# 07_USB_OTG.net
KiCad netlist of a schematic drawn in Altium Designer
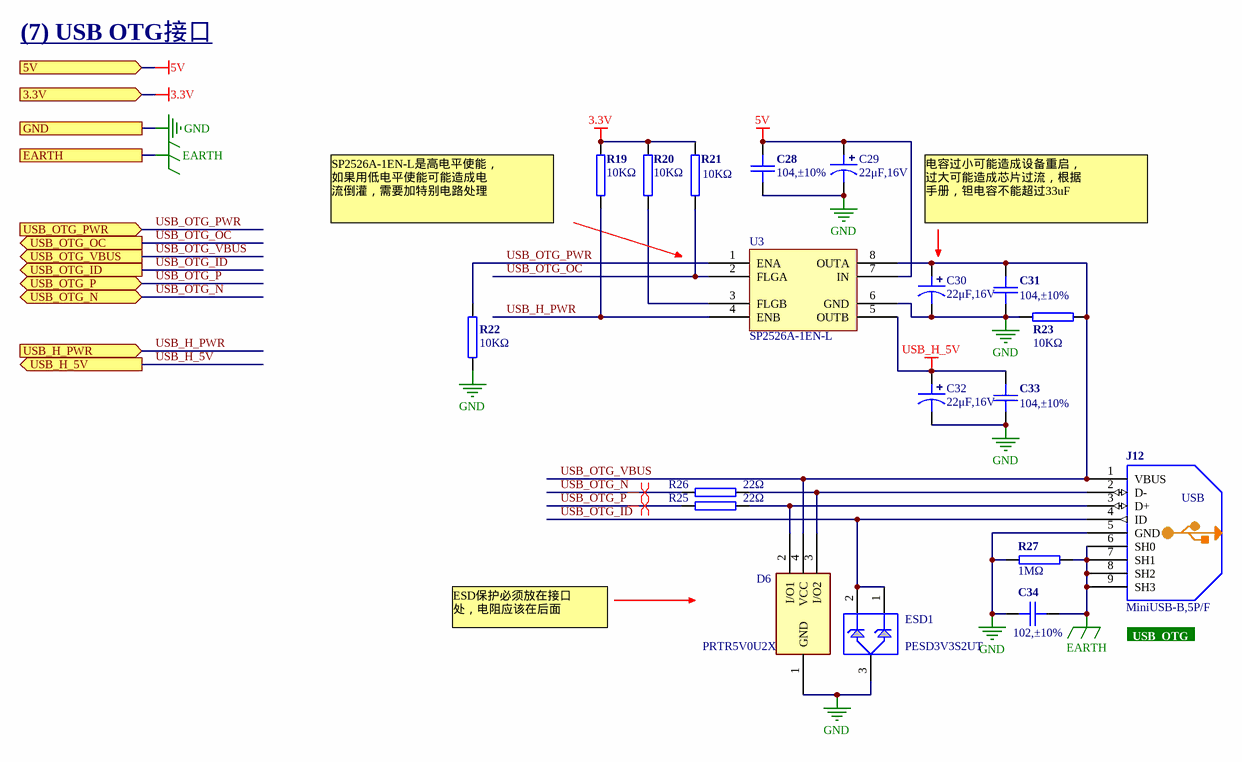
[diagram p0: 07. USB OTG.SchDoc]

(export (version "E")
  (design (tool "Eeschema 10.0.6"))
  (components
    (comp (ref "C28")
      (value "104,±10%")
      (footprint "0603C")
      (description "Capacitor")
      (libsource (lib "ErpMaterialData") (part "CAP1"))
    )
    (comp (ref "C29")
      (value "22μF,16V")
      (footprint "CAP-B")
      (description "22μF,16V,B型,,AVX,RoHS")
      (libsource (lib "ErpMaterialData") (part "CAPACITOR"))
    )
    (comp (ref "C30")
      (value "22μF,16V")
      (footprint "CAP-B")
      (description "22μF,16V,B型,,AVX,RoHS")
      (libsource (lib "ErpMaterialData") (part "CAPACITOR"))
    )
    (comp (ref "C31")
      (value "104,±10%")
      (footprint "0603C")
      (description "Capacitor")
      (libsource (lib "ErpMaterialData") (part "CAP1"))
    )
    (comp (ref "C32")
      (value "22μF,16V")
      (footprint "CAP-B")
      (description "22μF,16V,B型,,AVX,RoHS")
      (libsource (lib "ErpMaterialData") (part "CAPACITOR"))
    )
    (comp (ref "C33")
      (value "104,±10%")
      (footprint "0603C")
      (description "Capacitor")
      (libsource (lib "ErpMaterialData") (part "CAP1"))
    )
    (comp (ref "C34")
      (value "102,±10%")
      (footprint "1206C")
      (description "Capacitor")
      (libsource (lib "ErpMaterialData") (part "CAP1"))
    )
    (comp (ref "D6")
      (value "PRTR5V0U2X")
      (footprint "SOT-143")
      (description "PRTR5V0U2X,SOT-143B,NXP,RoHS")
      (libsource (lib "ErpMaterialData") (part "PRTR5V0U2X"))
    )
    (comp (ref "ESD1")
      (value "PESD3V3S2UT")
      (footprint "SOT-23")
      (description "PESD3V3S2UT,SOT-23,NXP,RoHS")
      (fields (field (name "Comment") "ESD-3"))
      (libsource (lib "ErpMaterialData") (part "ESD-3"))
    )
    (comp (ref "J12")
      (value "MiniUSB-B,5P/F")
      (footprint "USB_MINIB_SMT")
      (description "MiniUSB-B,5P/F,7.6×9×4,SMD,RoHS")
      (fields (field (name "Comment") "USB_MINIB_SMT"))
      (libsource (lib "ErpMaterialData") (part "USB_MINIB_SMT"))
    )
    (comp (ref "R19") (value "10KΩ") (footprint "0603R") (libsource (lib "ErpMaterialData") (part "RES2")))
    (comp (ref "R20") (value "10KΩ") (footprint "0603R") (libsource (lib "ErpMaterialData") (part "RES2")))
    (comp (ref "R21") (value "10KΩ") (footprint "0603R") (libsource (lib "ErpMaterialData") (part "RES2")))
    (comp (ref "R22") (value "10KΩ") (footprint "0603R") (libsource (lib "ErpMaterialData") (part "RES2")))
    (comp (ref "R23")
      (value "10KΩ")
      (footprint "0603R")
      (description "10KΩ,0603,*,RoHS")
      (libsource (lib "ErpMaterialData") (part "RES2"))
    )
    (comp (ref "R25") (value "22Ω") (footprint "0603R") (libsource (lib "ErpMaterialData") (part "RES2")))
    (comp (ref "R26") (value "22Ω") (footprint "0603R") (libsource (lib "ErpMaterialData") (part "RES2")))
    (comp (ref "R27") (value "1MΩ") (footprint "1206R") (libsource (lib "ErpMaterialData") (part "RES2")))
    (comp (ref "U3")
      (value "SP2526A-1EN-L")
      (footprint "SOIC127P600X175-8N")
      (description "SP2526A-1EN-L,SO-8,EXAR,RoHS")
      (fields (field (name "Comment") "SP2526A"))
      (libsource (lib "ErpMaterialData") (part "SP2526A"))
    )
  )
  (nets
    (net (code "1") (name "/USB_H_PWR") (class "Default")
      (node (ref "R19") (pin "1") (pinfunction "1_1") (pintype "passive"))
      (node (ref "U3") (pin "4") (pinfunction "ENB_4") (pintype "passive"))
    )
    (net (code "2") (name "/USB_OTG_ID") (class "Default")
      (node (ref "ESD1") (pin "1") (pinfunction "1_1") (pintype "passive"))
      (node (ref "ESD1") (pin "2") (pinfunction "2_2") (pintype "passive"))
      (node (ref "J12") (pin "4") (pinfunction "ID_4") (pintype "output"))
    )
    (net (code "3") (name "/USB_OTG_N") (class "Default")
      (node (ref "R26") (pin "2") (pinfunction "2_2") (pintype "passive"))
    )
    (net (code "4") (name "/USB_OTG_OC") (class "Default")
      (node (ref "R21") (pin "1") (pinfunction "1_1") (pintype "passive"))
      (node (ref "U3") (pin "2") (pinfunction "FLGA_2") (pintype "passive"))
    )
    (net (code "5") (name "/USB_OTG_P") (class "Default")
      (node (ref "R25") (pin "2") (pinfunction "2_2") (pintype "passive"))
    )
    (net (code "6") (name "/USB_OTG_PWR") (class "Default")
      (node (ref "R22") (pin "2") (pinfunction "2_2") (pintype "passive"))
      (node (ref "U3") (pin "1") (pinfunction "ENA_1") (pintype "passive"))
    )
    (net (code "7") (name "/USB_OTG_VBUS") (class "Default")
      (node (ref "C30") (pin "1") (pinfunction "1_1") (pintype "passive"))
      (node (ref "C31") (pin "2") (pinfunction "2_2") (pintype "passive"))
      (node (ref "D6") (pin "4") (pinfunction "VCC_4") (pintype "passive"))
      (node (ref "J12") (pin "1") (pinfunction "VBUS_1") (pintype "passive"))
      (node (ref "R23") (pin "1") (pinfunction "1_1") (pintype "passive"))
      (node (ref "U3") (pin "8") (pinfunction "OUTA_8") (pintype "passive"))
    )
    (net (code "8") (name "3.3V") (class "Default")
      (node (ref "R19") (pin "2") (pinfunction "2_2") (pintype "passive"))
      (node (ref "R20") (pin "2") (pinfunction "2_2") (pintype "passive"))
      (node (ref "R21") (pin "2") (pinfunction "2_2") (pintype "passive"))
    )
    (net (code "9") (name "5V") (class "Default")
      (node (ref "C28") (pin "1") (pinfunction "1_1") (pintype "passive"))
      (node (ref "C29") (pin "1") (pinfunction "1_1") (pintype "passive"))
      (node (ref "U3") (pin "7") (pinfunction "IN_7") (pintype "passive"))
    )
    (net (code "10") (name "EARTH") (class "Default")
      (node (ref "C34") (pin "2") (pinfunction "2_2") (pintype "passive"))
      (node (ref "J12") (pin "6") (pinfunction "SH0_6") (pintype "passive"))
      (node (ref "J12") (pin "7") (pinfunction "SH1_7") (pintype "passive"))
      (node (ref "J12") (pin "8") (pinfunction "SH2_8") (pintype "passive"))
      (node (ref "J12") (pin "9") (pinfunction "SH3_9") (pintype "passive"))
      (node (ref "R27") (pin "2") (pinfunction "2_2") (pintype "passive"))
    )
    (net (code "11") (name "GND") (class "Default")
      (node (ref "C28") (pin "2") (pinfunction "2_2") (pintype "passive"))
      (node (ref "C29") (pin "2") (pinfunction "2_2") (pintype "passive"))
      (node (ref "C30") (pin "2") (pinfunction "2_2") (pintype "passive"))
      (node (ref "C31") (pin "1") (pinfunction "1_1") (pintype "passive"))
      (node (ref "C32") (pin "2") (pinfunction "2_2") (pintype "passive"))
      (node (ref "C33") (pin "1") (pinfunction "1_1") (pintype "passive"))
      (node (ref "C34") (pin "1") (pinfunction "1_1") (pintype "passive"))
      (node (ref "D6") (pin "1") (pinfunction "GND_1") (pintype "passive"))
      (node (ref "ESD1") (pin "3") (pinfunction "3_3") (pintype "passive"))
      (node (ref "J12") (pin "5") (pinfunction "GND_5") (pintype "power_in"))
      (node (ref "R22") (pin "1") (pinfunction "1_1") (pintype "passive"))
      (node (ref "R23") (pin "2") (pinfunction "2_2") (pintype "passive"))
      (node (ref "R27") (pin "1") (pinfunction "1_1") (pintype "passive"))
      (node (ref "U3") (pin "6") (pinfunction "GND_6") (pintype "passive"))
    )
    (net (code "12") (name "Net-(D6-I{slash}O1)") (class "Default")
      (node (ref "D6") (pin "2") (pinfunction "I/O1_2") (pintype "passive"))
      (node (ref "J12") (pin "3") (pinfunction "D+_3") (pintype "bidirectional"))
      (node (ref "R25") (pin "1") (pinfunction "1_1") (pintype "passive"))
    )
    (net (code "13") (name "Net-(D6-I{slash}O2)") (class "Default")
      (node (ref "D6") (pin "3") (pinfunction "I/O2_3") (pintype "passive"))
      (node (ref "J12") (pin "2") (pinfunction "D-_2") (pintype "bidirectional"))
      (node (ref "R26") (pin "1") (pinfunction "1_1") (pintype "passive"))
    )
    (net (code "14") (name "Net-(U3-FLGB)") (class "Default")
      (node (ref "R20") (pin "1") (pinfunction "1_1") (pintype "passive"))
      (node (ref "U3") (pin "3") (pinfunction "FLGB_3") (pintype "passive"))
    )
    (net (code "15") (name "USB_H_5V") (class "Default")
      (node (ref "C32") (pin "1") (pinfunction "1_1") (pintype "passive"))
      (node (ref "C33") (pin "2") (pinfunction "2_2") (pintype "passive"))
      (node (ref "U3") (pin "5") (pinfunction "OUTB_5") (pintype "passive"))
    )
  )
)
